# Connectors.net
KiCad netlist of a schematic drawn in Altium Designer
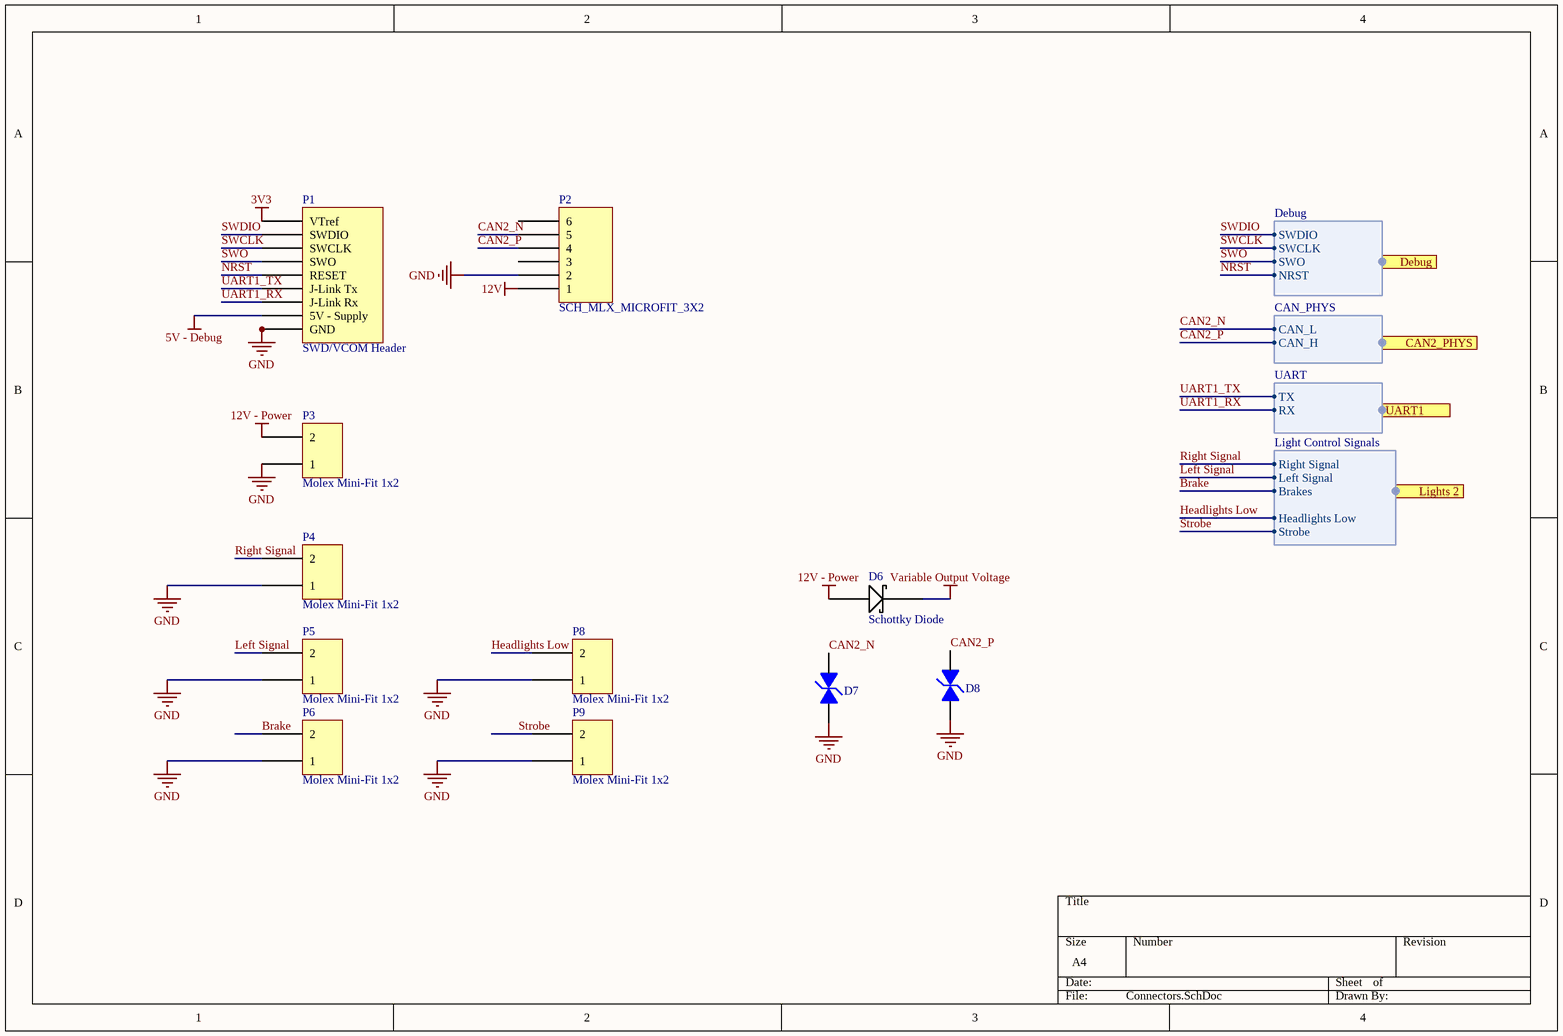
[diagram p0: Connectors.SchDoc]

(export (version "E")
  (design (tool "Eeschema 10.0.6"))
  (components
    (comp (ref "D6")
      (value "Schottky Diode")
      (footprint "ON Semi Schottky Diode - MBRM110LT1G")
      (libsource (lib "ON Semi Schottky Diode") (part "ON Semi Schottky Diode - MBRM110LT1G"))
    )
    (comp (ref "D7")
      (value "TVS Diode")
      (footprint "TVS Diode")
      (fields (field (name "MANUFACTURER") "Bourns"))
      (libsource (lib "TVS Diode") (part "TVS Diode"))
    )
    (comp (ref "D8")
      (value "TVS Diode")
      (footprint "TVS Diode")
      (fields (field (name "MANUFACTURER") "Bourns"))
      (libsource (lib "TVS Diode") (part "TVS Diode"))
    )
    (comp (ref "P1")
      (value "SWD/VCOM Header")
      (footprint "Samtec TST-110-01-G-D")
      (libsource (lib "SWD+VCOM Header - J-Link") (part "SWD/VCOM Header"))
    )
    (comp (ref "P2")
      (value "SCH_MLX_MICROFIT_3X2")
      (footprint "Molex Microfit 3.0 3x2:PCB_MLX_MICROFIT_3X2")
      (libsource (lib "Molex Microfit 3.0 3x2") (part "SCH_MLX_MICROFIT_3X2"))
    )
    (comp (ref "P3")
      (value "Molex Mini-Fit 1x2")
      (footprint "Molex Mini-Fit Jr 2x1")
      (libsource (lib "Molex Mini-Fit Jr 1x2") (part "Molex Mini-Fit 1x2"))
    )
    (comp (ref "P4")
      (value "Molex Mini-Fit 1x2")
      (footprint "Molex Mini-Fit Jr 2x1")
      (libsource (lib "Molex Mini-Fit Jr 1x2") (part "Molex Mini-Fit 1x2"))
    )
    (comp (ref "P5")
      (value "Molex Mini-Fit 1x2")
      (footprint "Molex Mini-Fit Jr 2x1")
      (libsource (lib "Molex Mini-Fit Jr 1x2") (part "Molex Mini-Fit 1x2"))
    )
    (comp (ref "P6")
      (value "Molex Mini-Fit 1x2")
      (footprint "Molex Mini-Fit Jr 2x1")
      (libsource (lib "Molex Mini-Fit Jr 1x2") (part "Molex Mini-Fit 1x2"))
    )
    (comp (ref "P8")
      (value "Molex Mini-Fit 1x2")
      (footprint "Molex Mini-Fit Jr 2x1")
      (libsource (lib "Molex Mini-Fit Jr 1x2") (part "Molex Mini-Fit 1x2"))
    )
    (comp (ref "P9")
      (value "Molex Mini-Fit 1x2")
      (footprint "Molex Mini-Fit Jr 2x1")
      (libsource (lib "Molex Mini-Fit Jr 1x2") (part "Molex Mini-Fit 1x2"))
    )
  )
  (nets
    (net (code "7") (name "/Brake") (class "Default")
      (node (ref "P6") (pin "2") (pinfunction "2_2") (pintype "passive"))
    )
    (net (code "8") (name "/CAN2_N") (class "Default")
      (node (ref "D7") (pin "1") (pintype "passive"))
      (node (ref "P2") (pin "5") (pinfunction "5_5") (pintype "passive"))
    )
    (net (code "9") (name "/CAN2_P") (class "Default")
      (node (ref "D8") (pin "1") (pintype "passive"))
      (node (ref "P2") (pin "4") (pinfunction "4_4") (pintype "passive"))
    )
    (net (code "10") (name "/Headlights Low") (class "Default")
      (node (ref "P8") (pin "2") (pinfunction "2_2") (pintype "passive"))
    )
    (net (code "11") (name "/Left Signal") (class "Default")
      (node (ref "P5") (pin "2") (pinfunction "2_2") (pintype "passive"))
    )
    (net (code "12") (name "/NRST") (class "Default")
      (node (ref "P1") (pin "15") (pinfunction "RESET_15") (pintype "passive"))
    )
    (net (code "13") (name "/Right Signal") (class "Default")
      (node (ref "P4") (pin "2") (pinfunction "2_2") (pintype "passive"))
    )
    (net (code "14") (name "/SWCLK") (class "Default")
      (node (ref "P1") (pin "9") (pinfunction "SWCLK_9") (pintype "passive"))
    )
    (net (code "15") (name "/SWDIO") (class "Default")
      (node (ref "P1") (pin "7") (pinfunction "SWDIO_7") (pintype "passive"))
    )
    (net (code "16") (name "/SWO") (class "Default")
      (node (ref "P1") (pin "13") (pinfunction "SWO_13") (pintype "passive"))
    )
    (net (code "17") (name "/Strobe") (class "Default")
      (node (ref "P9") (pin "2") (pinfunction "2_2") (pintype "passive"))
    )
    (net (code "18") (name "/UART1_RX") (class "Default")
      (node (ref "P1") (pin "17") (pinfunction "J-Link_Rx_17") (pintype "passive"))
    )
    (net (code "19") (name "/UART1_TX") (class "Default")
      (node (ref "P1") (pin "5") (pinfunction "J-Link_Tx_5") (pintype "passive"))
    )
    (net (code "24") (name "3V3") (class "Default")
      (node (ref "P1") (pin "1") (pinfunction "VTref_1") (pintype "passive"))
    )
    (net (code "25") (name "5V - Debug") (class "Default")
      (node (ref "P1") (pin "19") (pinfunction "5V_-_Supply_19") (pintype "passive"))
    )
    (net (code "26") (name "12V") (class "Default")
      (node (ref "P2") (pin "1") (pinfunction "1_1") (pintype "passive"))
    )
    (net (code "27") (name "12V - Power") (class "Default")
      (node (ref "D6") (pin "2") (pinfunction "2_2") (pintype "passive"))
      (node (ref "P3") (pin "2") (pinfunction "2_2") (pintype "passive"))
    )
    (net (code "28") (name "GND") (class "Default")
      (node (ref "D7") (pin "2") (pintype "passive"))
      (node (ref "D8") (pin "2") (pintype "passive"))
      (node (ref "P1") (pin "10") (pinfunction "GND_10") (pintype "passive"))
      (node (ref "P1") (pin "12") (pinfunction "GND_12") (pintype "passive"))
      (node (ref "P1") (pin "4") (pinfunction "GND_4") (pintype "passive"))
      (node (ref "P1") (pin "6") (pinfunction "GND_6") (pintype "passive"))
      (node (ref "P1") (pin "8") (pinfunction "GND_8") (pintype "passive"))
      (node (ref "P2") (pin "2") (pinfunction "2_2") (pintype "passive"))
      (node (ref "P3") (pin "1") (pinfunction "1_1") (pintype "passive"))
      (node (ref "P4") (pin "1") (pinfunction "1_1") (pintype "passive"))
      (node (ref "P5") (pin "1") (pinfunction "1_1") (pintype "passive"))
      (node (ref "P6") (pin "1") (pinfunction "1_1") (pintype "passive"))
      (node (ref "P8") (pin "1") (pinfunction "1_1") (pintype "passive"))
      (node (ref "P9") (pin "1") (pinfunction "1_1") (pintype "passive"))
    )
    (net (code "29") (name "Variable Output Voltage") (class "Default")
      (node (ref "D6") (pin "1") (pinfunction "1_1") (pintype "passive"))
    )
    (net (code "30") (name "unconnected-(P2-Pad3)") (class "Default")
      (node (ref "P2") (pin "3") (pinfunction "3_3") (pintype "passive"))
    )
    (net (code "31") (name "unconnected-(P2-Pad6)") (class "Default")
      (node (ref "P2") (pin "6") (pinfunction "6_6") (pintype "passive"))
    )
  )
)
